# schematic.net
KiCad netlist of a schematic drawn in EasyEDA
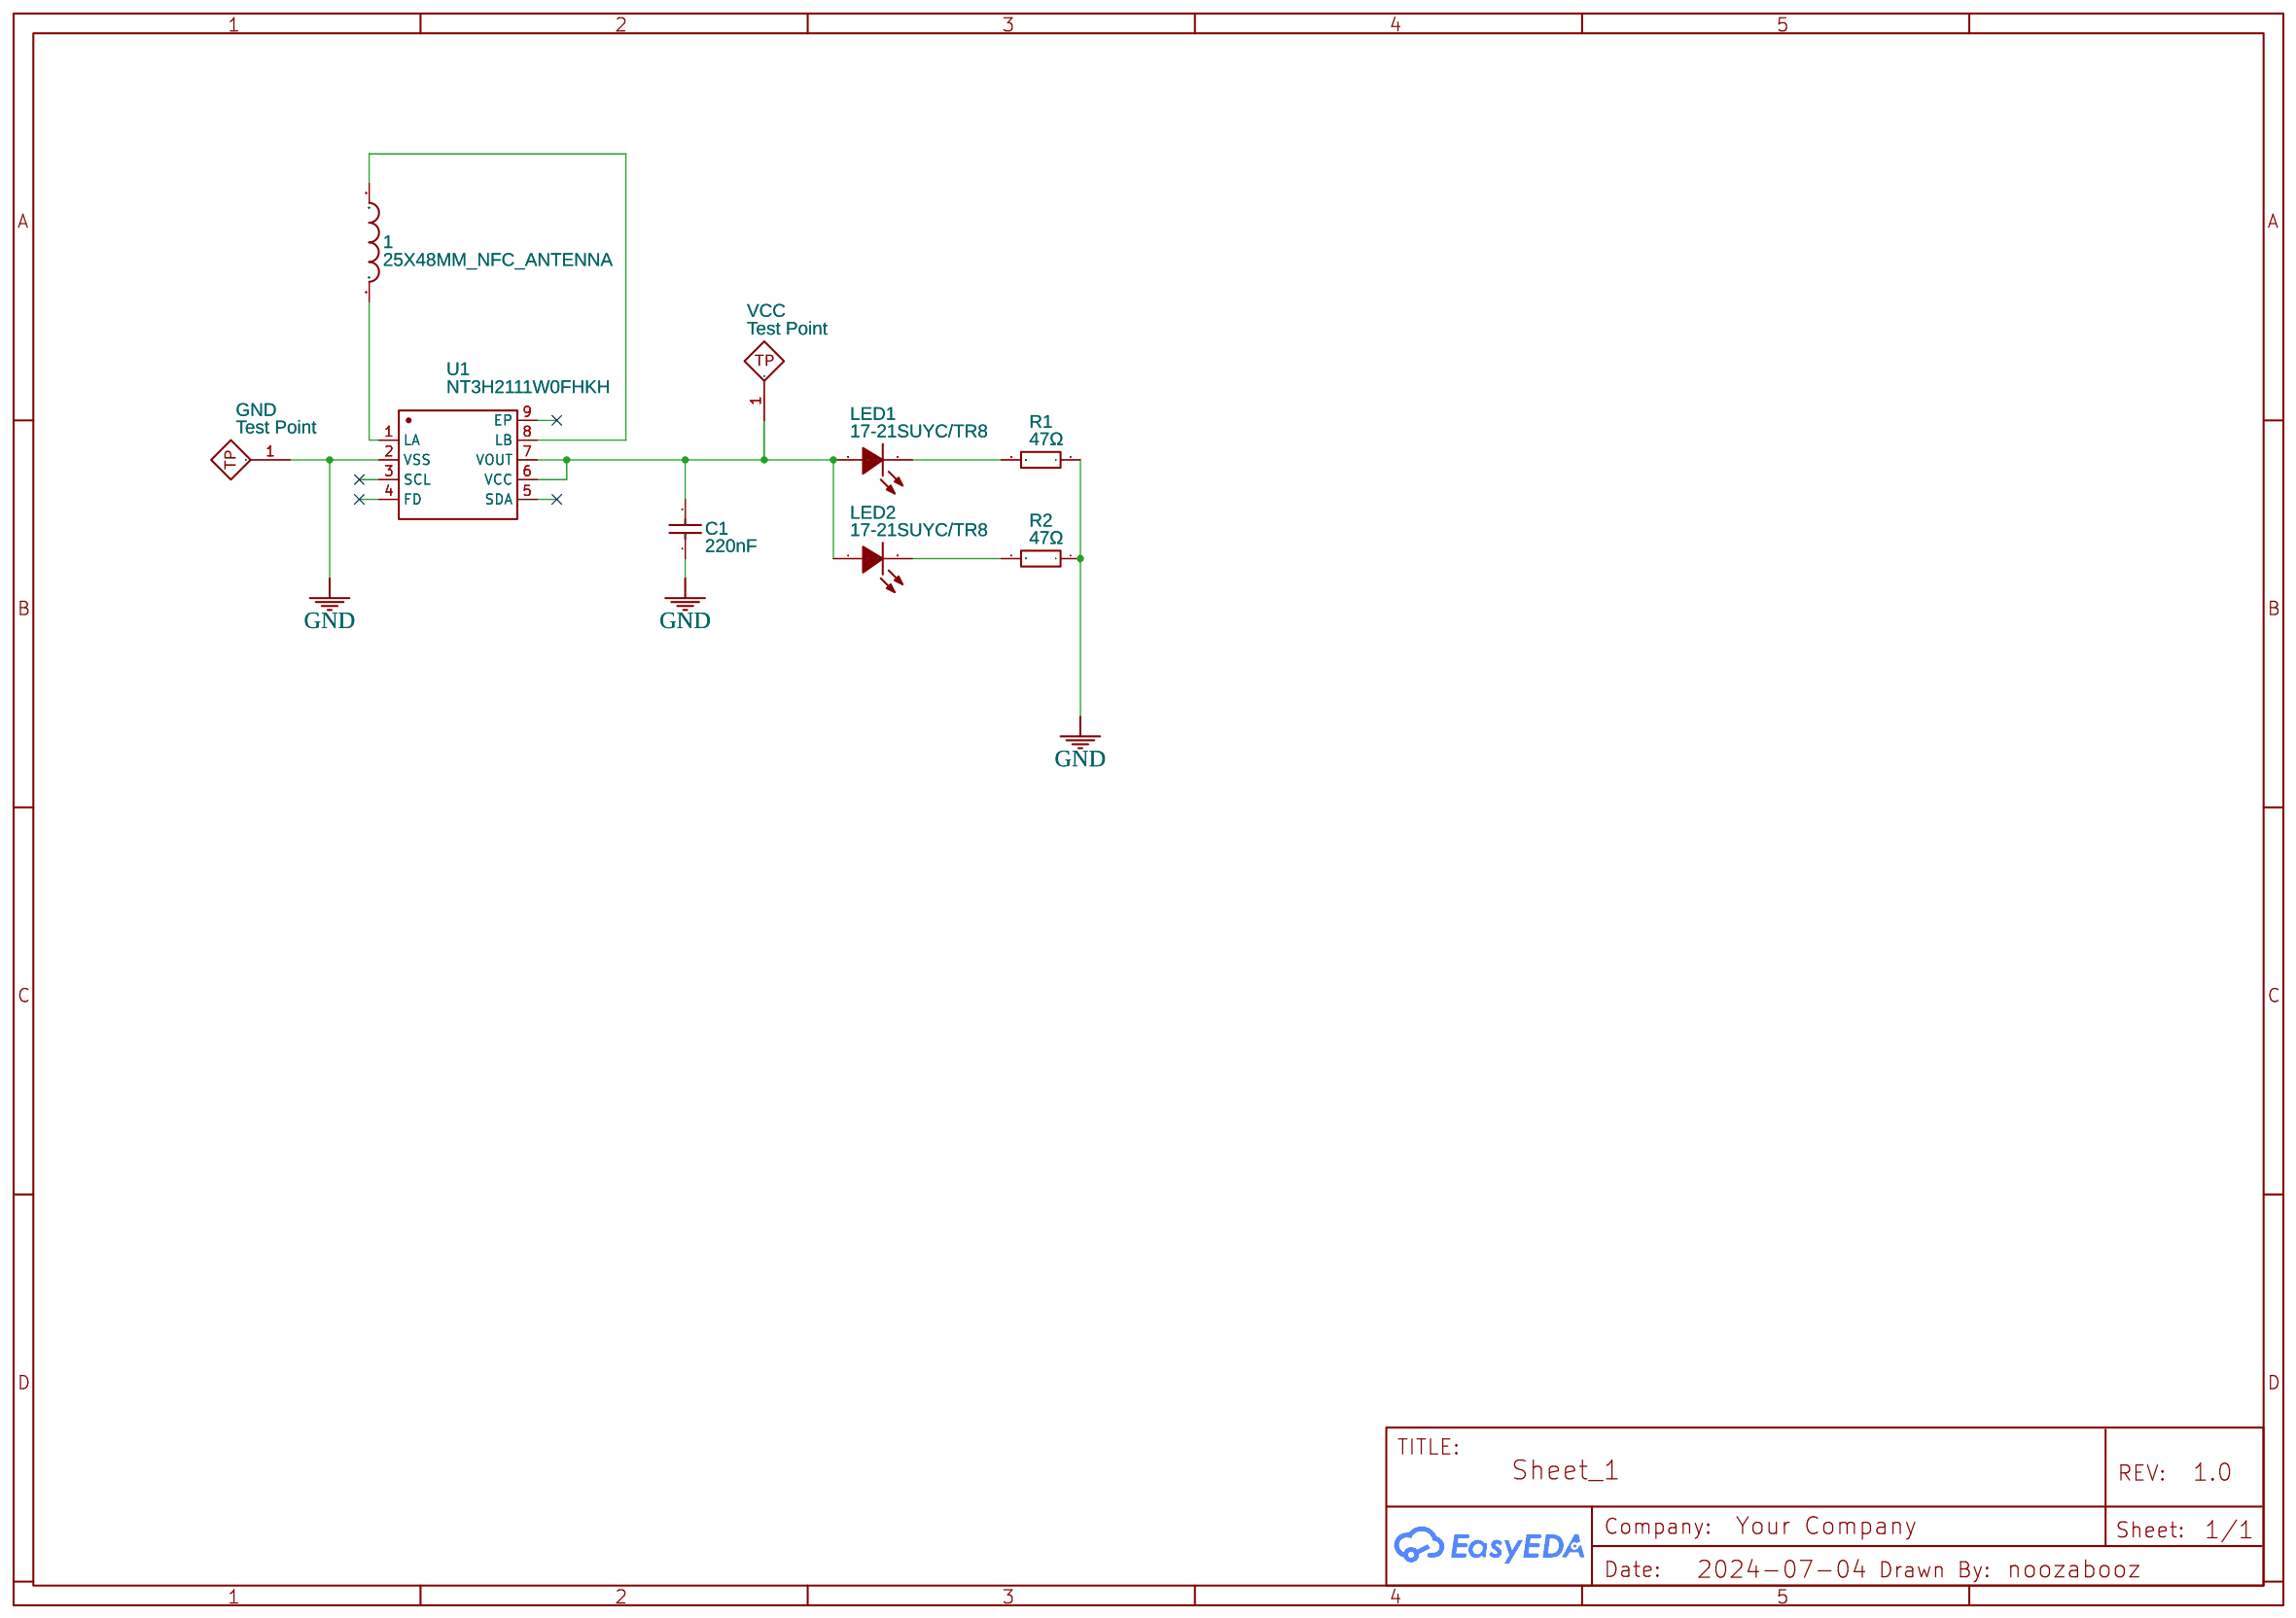
[diagram p0: schematic sheet]

(export (version "E")
  (design (tool "Eeschema 10.0.6"))
  (components
    (comp (ref "1") (value "25X48MM_NFC_ANTENNA") (libsource (lib "") (part "25X48MM_NFC_ANTENNA")))
    (comp (ref "C1")
      (value "220nF")
      (fields
        (field (name "Manufacturer Part") "CL10B224KA8NNNC")
        (field (name "Manufacturer") "SAMSUNG(三星)")
      )
      (libsource (lib "") (part "CL10B224KA8NNNC"))
    )
    (comp (ref "GND") (value "Test Point") (libsource (lib "") (part "Test Point_1")))
    (comp (ref "LED1")
      (value "17-21SUYC/TR8")
      (fields (field (name "Manufacturer Part") "KT-0805黄灯") (field (name "Manufacturer") "KENTO"))
      (libsource (lib "") (part "17-21SUYC/TR8"))
    )
    (comp (ref "LED2")
      (value "17-21SUYC/TR8")
      (fields (field (name "Manufacturer Part") "KT-0805黄灯") (field (name "Manufacturer") "KENTO"))
      (libsource (lib "") (part "17-21SUYC/TR8"))
    )
    (comp (ref "R1")
      (value "47Ω")
      (fields
        (field (name "Manufacturer Part") "0603WAF470JT5E")
        (field (name "Manufacturer") "UNI-ROYAL(厚声)")
      )
      (libsource (lib "") (part "0603WAF470JT5E"))
    )
    (comp (ref "R2")
      (value "47Ω")
      (fields
        (field (name "Manufacturer Part") "0603WAF470JT5E")
        (field (name "Manufacturer") "UNI-ROYAL(厚声)")
      )
      (libsource (lib "") (part "0603WAF470JT5E"))
    )
    (comp (ref "U1")
      (value "NT3H2111W0FHKH")
      (fields (field (name "Manufacturer") "NXP(恩智浦)"))
      (libsource (lib "") (part "NT3H2111W0FHKH"))
    )
    (comp (ref "VCC") (value "Test Point") (libsource (lib "") (part "Test Point")))
  )
  (nets
    (net (code "1") (name "GND") (class "Default")
      (node (ref "C1") (pin "1") (pinfunction "1_1") (pintype "input"))
      (node (ref "GND") (pin "1") (pinfunction "1_1") (pintype "unspecified"))
      (node (ref "R1") (pin "1") (pinfunction "1_1") (pintype "input"))
      (node (ref "R2") (pin "1") (pinfunction "1_1") (pintype "input"))
      (node (ref "U1") (pin "2") (pinfunction "VSS_2") (pintype "unspecified"))
    )
    (net (code "2") (name "Net-(LED1-+)") (class "Default")
      (node (ref "C1") (pin "2") (pinfunction "2_2") (pintype "input"))
      (node (ref "LED1") (pin "1") (pinfunction "+_1") (pintype "unspecified"))
      (node (ref "LED2") (pin "1") (pinfunction "+_1") (pintype "unspecified"))
      (node (ref "U1") (pin "6") (pinfunction "VCC_6") (pintype "unspecified"))
      (node (ref "U1") (pin "7") (pinfunction "VOUT_7") (pintype "unspecified"))
      (node (ref "VCC") (pin "1") (pinfunction "1_1") (pintype "unspecified"))
    )
    (net (code "3") (name "Net-(LED1--)") (class "Default")
      (node (ref "LED1") (pin "2") (pinfunction "-_2") (pintype "unspecified"))
      (node (ref "R1") (pin "2") (pinfunction "2_2") (pintype "input"))
    )
    (net (code "4") (name "Net-(LED2--)") (class "Default")
      (node (ref "LED2") (pin "2") (pinfunction "-_2") (pintype "unspecified"))
      (node (ref "R2") (pin "2") (pinfunction "2_2") (pintype "input"))
    )
    (net (code "5") (name "Net-(U1-LA)") (class "Default")
      (node (ref "1") (pin "P$2") (pinfunction "P$2_P$2") (pintype "bidirectional"))
      (node (ref "U1") (pin "1") (pinfunction "LA_1") (pintype "unspecified"))
    )
    (net (code "6") (name "Net-(U1-LB)") (class "Default")
      (node (ref "1") (pin "P$1") (pinfunction "P$1_P$1") (pintype "bidirectional"))
      (node (ref "U1") (pin "8") (pinfunction "LB_8") (pintype "unspecified"))
    )
    (net (code "7") (name "unconnected-(U1-EP-Pad9)") (class "Default")
      (node (ref "U1") (pin "9") (pinfunction "EP_9") (pintype "unspecified+no_connect"))
    )
    (net (code "8") (name "unconnected-(U1-FD-Pad4)") (class "Default")
      (node (ref "U1") (pin "4") (pinfunction "FD_4") (pintype "unspecified+no_connect"))
    )
    (net (code "9") (name "unconnected-(U1-SCL-Pad3)") (class "Default")
      (node (ref "U1") (pin "3") (pinfunction "SCL_3") (pintype "unspecified+no_connect"))
    )
    (net (code "10") (name "unconnected-(U1-SDA-Pad5)") (class "Default")
      (node (ref "U1") (pin "5") (pinfunction "SDA_5") (pintype "unspecified+no_connect"))
    )
  )
)
